# CAT6_snake_2ch.net
KiCad netlist of a schematic drawn in EAGLE
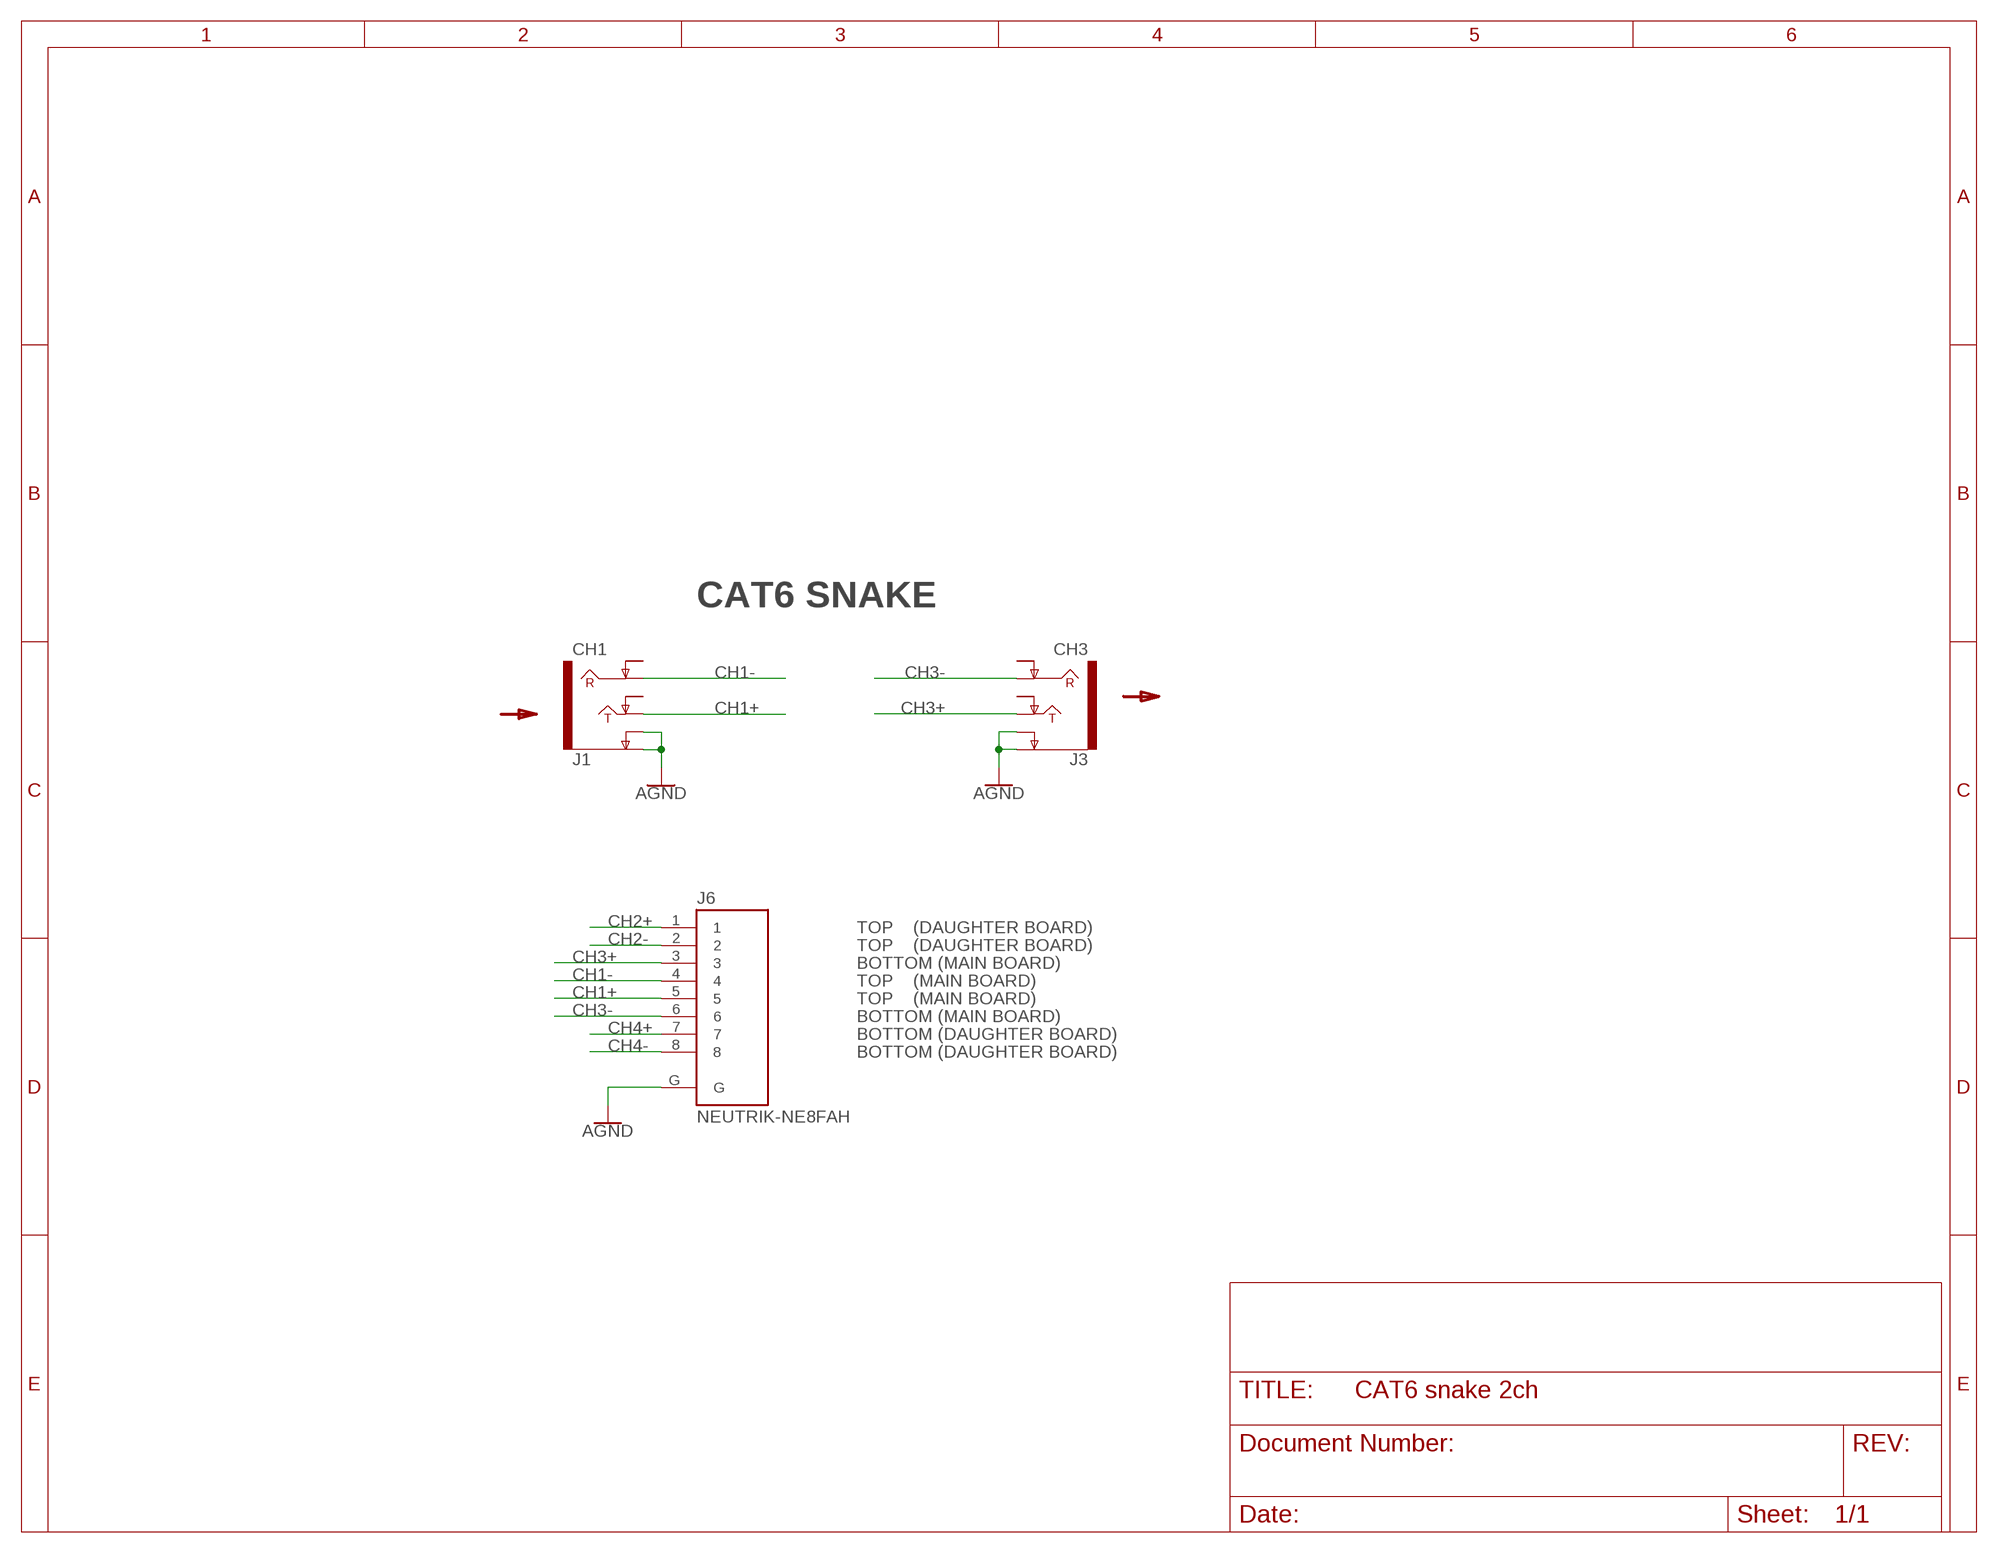
[diagram p0: schematic, sheet 1]

(export (version "E")
  (design (tool "Eeschema 10.0.6"))
  (components
    (comp (ref "J1")
      (value "CH1")
      (footprint "eagle-import:NEUTRIK-NRJ6HF")
      (libsource (lib "eagle-import") (part "AUDIO_JACK_TRS_0.25{dblquote}_PTH_RA-NRJ6HM"))
    )
    (comp (ref "J3")
      (value "CH3")
      (footprint "eagle-import:NEUTRIK-NRJ6HF")
      (libsource (lib "eagle-import") (part "AUDIO_JACK_TRS_0.25{dblquote}_PTH_RA-NRJ6HM"))
    )
    (comp (ref "J6")
      (value "NEUTRIK-NE8FAH")
      (footprint "eagle-import:NEUTRIK_NE8FAH")
      (fields (field (name "MF") "Neutrik") (field (name "MP") "NE8FAH"))
      (libsource (lib "eagle-import") (part "NEUTRIK-NE8FAH"))
    )
  )
  (nets
    (net (code "1") (name "/CH1+") (class "Default")
      (node (ref "J1") (pin "T") (pinfunction "TIP_T") (pintype "bidirectional"))
      (node (ref "J6") (pin "5") (pinfunction "5_5") (pintype "passive"))
    )
    (net (code "2") (name "/CH1-") (class "Default")
      (node (ref "J1") (pin "R") (pinfunction "RING_R") (pintype "bidirectional"))
      (node (ref "J6") (pin "4") (pinfunction "4_4") (pintype "passive"))
    )
    (net (code "3") (name "/CH2+") (class "Default")
      (node (ref "J6") (pin "1") (pinfunction "1_1") (pintype "passive"))
    )
    (net (code "4") (name "/CH2-") (class "Default")
      (node (ref "J6") (pin "2") (pinfunction "2_2") (pintype "passive"))
    )
    (net (code "5") (name "/CH3+") (class "Default")
      (node (ref "J3") (pin "T") (pinfunction "TIP_T") (pintype "bidirectional"))
      (node (ref "J6") (pin "3") (pinfunction "3_3") (pintype "passive"))
    )
    (net (code "6") (name "/CH3-") (class "Default")
      (node (ref "J3") (pin "R") (pinfunction "RING_R") (pintype "bidirectional"))
      (node (ref "J6") (pin "6") (pinfunction "6_6") (pintype "passive"))
    )
    (net (code "7") (name "/CH4+") (class "Default")
      (node (ref "J6") (pin "7") (pinfunction "7_7") (pintype "passive"))
    )
    (net (code "8") (name "/CH4-") (class "Default")
      (node (ref "J6") (pin "8") (pinfunction "8_8") (pintype "passive"))
    )
    (net (code "9") (name "AGND") (class "Default")
      (node (ref "J1") (pin "S") (pinfunction "EARTH_S") (pintype "bidirectional"))
      (node (ref "J1") (pin "SN") (pinfunction "EARTH-NORM_SN") (pintype "bidirectional"))
      (node (ref "J3") (pin "S") (pinfunction "EARTH_S") (pintype "bidirectional"))
      (node (ref "J3") (pin "SN") (pinfunction "EARTH-NORM_SN") (pintype "bidirectional"))
      (node (ref "J6") (pin "G") (pinfunction "G_G") (pintype "power_in"))
    )
    (net (code "10") (name "unconnected-(J1-RING-NORM-PadRN)") (class "Default")
      (node (ref "J1") (pin "RN") (pinfunction "RING-NORM_RN") (pintype "bidirectional"))
    )
    (net (code "11") (name "unconnected-(J1-TIP-NORM-PadTN)") (class "Default")
      (node (ref "J1") (pin "TN") (pinfunction "TIP-NORM_TN") (pintype "bidirectional"))
    )
    (net (code "12") (name "unconnected-(J3-RING-NORM-PadRN)") (class "Default")
      (node (ref "J3") (pin "RN") (pinfunction "RING-NORM_RN") (pintype "bidirectional"))
    )
    (net (code "13") (name "unconnected-(J3-TIP-NORM-PadTN)") (class "Default")
      (node (ref "J3") (pin "TN") (pinfunction "TIP-NORM_TN") (pintype "bidirectional"))
    )
  )
)
